# SDCard.net
KiCad netlist of a schematic drawn in Altium Designer
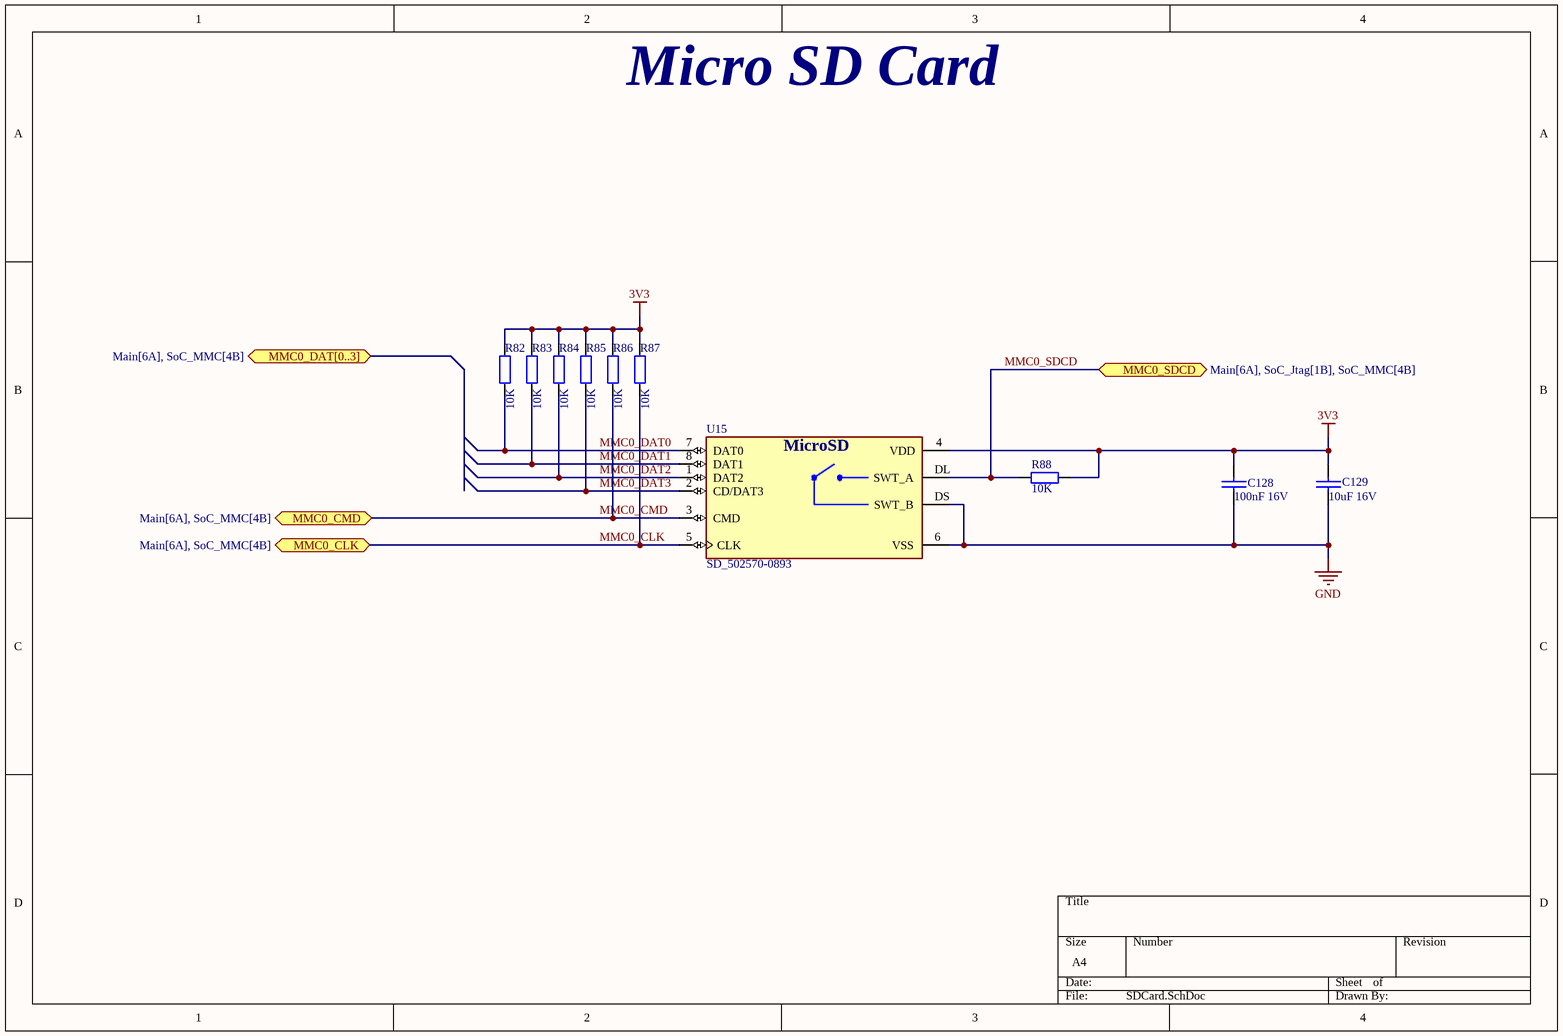
[diagram p0: SDCard.SchDoc]

(export (version "E")
  (design (tool "Eeschema 10.0.6"))
  (components
    (comp (ref "C128")
      (value "100nF 16V")
      (footprint "C_0402")
      (description "Capacitor 0402 SMD")
      (libsource (lib "tor1kkLib") (part "C_0402"))
    )
    (comp (ref "C129")
      (value "10uF 16V")
      (footprint "C_0603")
      (description "Capacitor 0603 SMD")
      (libsource (lib "tor1kkLib") (part "C_0603"))
    )
    (comp (ref "R82")
      (value "10K")
      (footprint "R_0402")
      (description "Resistor 0402 SMD")
      (libsource (lib "tor1kkLib") (part "R_0402"))
    )
    (comp (ref "R83")
      (value "10K")
      (footprint "R_0402")
      (description "Resistor 0402 SMD")
      (libsource (lib "tor1kkLib") (part "R_0402"))
    )
    (comp (ref "R84")
      (value "10K")
      (footprint "R_0402")
      (description "Resistor 0402 SMD")
      (libsource (lib "tor1kkLib") (part "R_0402"))
    )
    (comp (ref "R85")
      (value "10K")
      (footprint "R_0402")
      (description "Resistor 0402 SMD")
      (libsource (lib "tor1kkLib") (part "R_0402"))
    )
    (comp (ref "R86")
      (value "10K")
      (footprint "R_0402")
      (description "Resistor 0402 SMD")
      (libsource (lib "tor1kkLib") (part "R_0402"))
    )
    (comp (ref "R87")
      (value "10K")
      (footprint "R_0402")
      (description "Resistor 0402 SMD")
      (libsource (lib "tor1kkLib") (part "R_0402"))
    )
    (comp (ref "R88")
      (value "10K")
      (footprint "R_0402")
      (description "Resistor 0402 SMD")
      (libsource (lib "") (part "R_0402_1"))
    )
    (comp (ref "U15")
      (value "SD_502570-0893")
      (footprint "MOLEX_502570-0893")
      (fields (field (name "MANUFACTURER") "Molex") (field (name "MANUFACTURER PART NUMBER") "502570-0893"))
      (libsource (lib "tor1kkLib") (part "SD_502570-0893"))
    )
  )
  (nets
    (net (code "1") (name "/MMC0_CLK") (class "Default")
      (node (ref "R87") (pin "1") (pintype "passive"))
      (node (ref "U15") (pin "5") (pinfunction "CLK_5") (pintype "bidirectional"))
    )
    (net (code "2") (name "/MMC0_CMD") (class "Default")
      (node (ref "R86") (pin "1") (pintype "passive"))
      (node (ref "U15") (pin "3") (pinfunction "CMD_3") (pintype "bidirectional"))
    )
    (net (code "3") (name "/MMC0_DAT0") (class "Default")
      (node (ref "R82") (pin "1") (pintype "passive"))
      (node (ref "U15") (pin "7") (pinfunction "DAT0_7") (pintype "bidirectional"))
    )
    (net (code "4") (name "/MMC0_DAT1") (class "Default")
      (node (ref "R83") (pin "1") (pintype "passive"))
      (node (ref "U15") (pin "8") (pinfunction "DAT1_8") (pintype "bidirectional"))
    )
    (net (code "5") (name "/MMC0_DAT2") (class "Default")
      (node (ref "R84") (pin "1") (pintype "passive"))
      (node (ref "U15") (pin "1") (pinfunction "DAT2_1") (pintype "bidirectional"))
    )
    (net (code "6") (name "/MMC0_DAT3") (class "Default")
      (node (ref "R85") (pin "1") (pintype "passive"))
      (node (ref "U15") (pin "2") (pinfunction "CD/DAT3_2") (pintype "bidirectional"))
    )
    (net (code "8") (name "/MMC0_SDCD") (class "Default")
      (node (ref "R88") (pin "1") (pintype "passive"))
      (node (ref "U15") (pin "DL") (pinfunction "SWT_A_DL") (pintype "passive"))
    )
    (net (code "9") (name "3V3") (class "Default")
      (node (ref "C128") (pin "1") (pintype "passive"))
      (node (ref "C129") (pin "1") (pintype "passive"))
      (node (ref "R82") (pin "2") (pintype "passive"))
      (node (ref "R83") (pin "2") (pintype "passive"))
      (node (ref "R84") (pin "2") (pintype "passive"))
      (node (ref "R85") (pin "2") (pintype "passive"))
      (node (ref "R86") (pin "2") (pintype "passive"))
      (node (ref "R87") (pin "2") (pintype "passive"))
      (node (ref "R88") (pin "2") (pintype "passive"))
      (node (ref "U15") (pin "4") (pinfunction "VDD_4") (pintype "power_in"))
    )
    (net (code "10") (name "GND") (class "Default")
      (node (ref "C128") (pin "2") (pintype "passive"))
      (node (ref "C129") (pin "2") (pintype "passive"))
      (node (ref "U15") (pin "6") (pinfunction "VSS_6") (pintype "power_in"))
      (node (ref "U15") (pin "DS") (pinfunction "SWT_B_DS") (pintype "passive"))
    )
  )
)
